# ASIC.net
KiCad netlist of a schematic drawn in Altium Designer
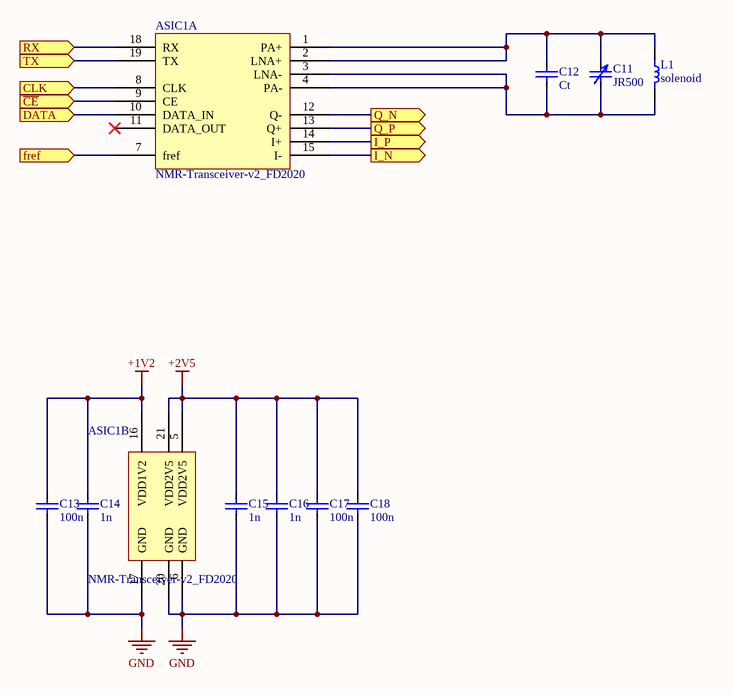
[diagram p0: ASIC.SchDoc]

(export (version "E")
  (design (tool "Eeschema 10.0.6"))
  (components
    (comp (ref "ASIC1")
      (value "NMR-Transceiver-v2_FD2020")
      (footprint "NMR-Transceiver-FD2020_Interposer-BGA")
      (libsource (lib "IIS-Lib_TW") (part "NMR-Transceiver-v2_FD2020"))
    )
    (comp (ref "C11") (value "JR500") (footprint "Cap_var") (libsource (lib "IIS-Lib_TW") (part "Cap_var")))
    (comp (ref "C12") (value "Ct") (footprint "CAP_0402") (libsource (lib "IIS-Lib_TW") (part "Cap")))
    (comp (ref "C13") (value "100n") (footprint "CAP_0402") (libsource (lib "IIS-Lib_TW") (part "Cap")))
    (comp (ref "C14") (value "1n") (footprint "CAP_0402") (libsource (lib "IIS-Lib_TW") (part "Cap")))
    (comp (ref "C15") (value "1n") (footprint "CAP_0402") (libsource (lib "IIS-Lib_TW") (part "Cap")))
    (comp (ref "C16") (value "1n") (footprint "CAP_0402") (libsource (lib "IIS-Lib_TW") (part "Cap")))
    (comp (ref "C17") (value "100n") (footprint "CAP_0402") (libsource (lib "IIS-Lib_TW") (part "Cap")))
    (comp (ref "C18") (value "100n") (footprint "CAP_0402") (libsource (lib "IIS-Lib_TW") (part "Cap")))
    (comp (ref "L1") (value "solenoid") (footprint "Ind_1206") (libsource (lib "IIS-Lib_TW") (part "Ind")))
  )
  (nets
    (net (code "1") (name "+1V2") (class "Default")
      (node (ref "ASIC1") (pin "16") (pinfunction "VDD1V2_16") (pintype "passive"))
      (node (ref "C13") (pin "1") (pinfunction "1_1") (pintype "passive"))
      (node (ref "C14") (pin "1") (pinfunction "1_1") (pintype "passive"))
    )
    (net (code "2") (name "+2V5") (class "Default")
      (node (ref "ASIC1") (pin "21") (pinfunction "VDD2V5_21") (pintype "passive"))
      (node (ref "ASIC1") (pin "5") (pinfunction "VDD2V5_5") (pintype "passive"))
      (node (ref "C15") (pin "1") (pinfunction "1_1") (pintype "passive"))
      (node (ref "C16") (pin "1") (pinfunction "1_1") (pintype "passive"))
      (node (ref "C17") (pin "1") (pinfunction "1_1") (pintype "passive"))
      (node (ref "C18") (pin "1") (pinfunction "1_1") (pintype "passive"))
    )
    (net (code "3") (name "/CLK") (class "Default")
      (node (ref "ASIC1") (pin "8") (pinfunction "CLK_8") (pintype "passive"))
    )
    (net (code "4") (name "/DATA") (class "Default")
      (node (ref "ASIC1") (pin "10") (pinfunction "DATA_IN_10") (pintype "passive"))
    )
    (net (code "5") (name "/I_N") (class "Default")
      (node (ref "ASIC1") (pin "15") (pinfunction "I-_15") (pintype "passive"))
    )
    (net (code "6") (name "/I_P") (class "Default")
      (node (ref "ASIC1") (pin "14") (pinfunction "I+_14") (pintype "passive"))
    )
    (net (code "7") (name "/Q_N") (class "Default")
      (node (ref "ASIC1") (pin "12") (pinfunction "Q-_12") (pintype "passive"))
    )
    (net (code "8") (name "/Q_P") (class "Default")
      (node (ref "ASIC1") (pin "13") (pinfunction "Q+_13") (pintype "passive"))
    )
    (net (code "9") (name "/RX") (class "Default")
      (node (ref "ASIC1") (pin "18") (pinfunction "RX_18") (pintype "passive"))
    )
    (net (code "10") (name "/TX") (class "Default")
      (node (ref "ASIC1") (pin "19") (pinfunction "TX_19") (pintype "passive"))
    )
    (net (code "11") (name "/fref") (class "Default")
      (node (ref "ASIC1") (pin "7") (pinfunction "fref_7") (pintype "passive"))
    )
    (net (code "12") (name "/~{CE}") (class "Default")
      (node (ref "ASIC1") (pin "9") (pinfunction "CE_9") (pintype "passive"))
    )
    (net (code "13") (name "GND") (class "Default")
      (node (ref "ASIC1") (pin "17") (pinfunction "GND_17") (pintype "passive"))
      (node (ref "ASIC1") (pin "20") (pinfunction "GND_20") (pintype "passive"))
      (node (ref "ASIC1") (pin "6") (pinfunction "GND_6") (pintype "passive"))
      (node (ref "C13") (pin "2") (pinfunction "2_2") (pintype "passive"))
      (node (ref "C14") (pin "2") (pinfunction "2_2") (pintype "passive"))
      (node (ref "C15") (pin "2") (pinfunction "2_2") (pintype "passive"))
      (node (ref "C16") (pin "2") (pinfunction "2_2") (pintype "passive"))
      (node (ref "C17") (pin "2") (pinfunction "2_2") (pintype "passive"))
      (node (ref "C18") (pin "2") (pinfunction "2_2") (pintype "passive"))
    )
    (net (code "14") (name "Net-(ASIC1A-LNA+)") (class "Default")
      (node (ref "ASIC1") (pin "1") (pinfunction "PA+_1") (pintype "passive"))
      (node (ref "ASIC1") (pin "2") (pinfunction "LNA+_2") (pintype "passive"))
      (node (ref "C11") (pin "1") (pinfunction "1_1") (pintype "passive"))
      (node (ref "C12") (pin "1") (pinfunction "1_1") (pintype "passive"))
      (node (ref "L1") (pin "1") (pinfunction "1_1") (pintype "passive"))
    )
    (net (code "15") (name "Net-(ASIC1A-LNA-)") (class "Default")
      (node (ref "ASIC1") (pin "3") (pinfunction "LNA-_3") (pintype "passive"))
      (node (ref "ASIC1") (pin "4") (pinfunction "PA-_4") (pintype "passive"))
      (node (ref "C11") (pin "2") (pinfunction "2_2") (pintype "passive"))
      (node (ref "C12") (pin "2") (pinfunction "2_2") (pintype "passive"))
      (node (ref "L1") (pin "2") (pinfunction "2_2") (pintype "passive"))
    )
    (net (code "16") (name "unconnected-(ASIC1A-DATA_OUT-Pad11)") (class "Default")
      (node (ref "ASIC1") (pin "11") (pinfunction "DATA_OUT_11") (pintype "passive+no_connect"))
    )
  )
)
